# Genesis_giraffe.net
KiCad netlist of a schematic drawn in EAGLE
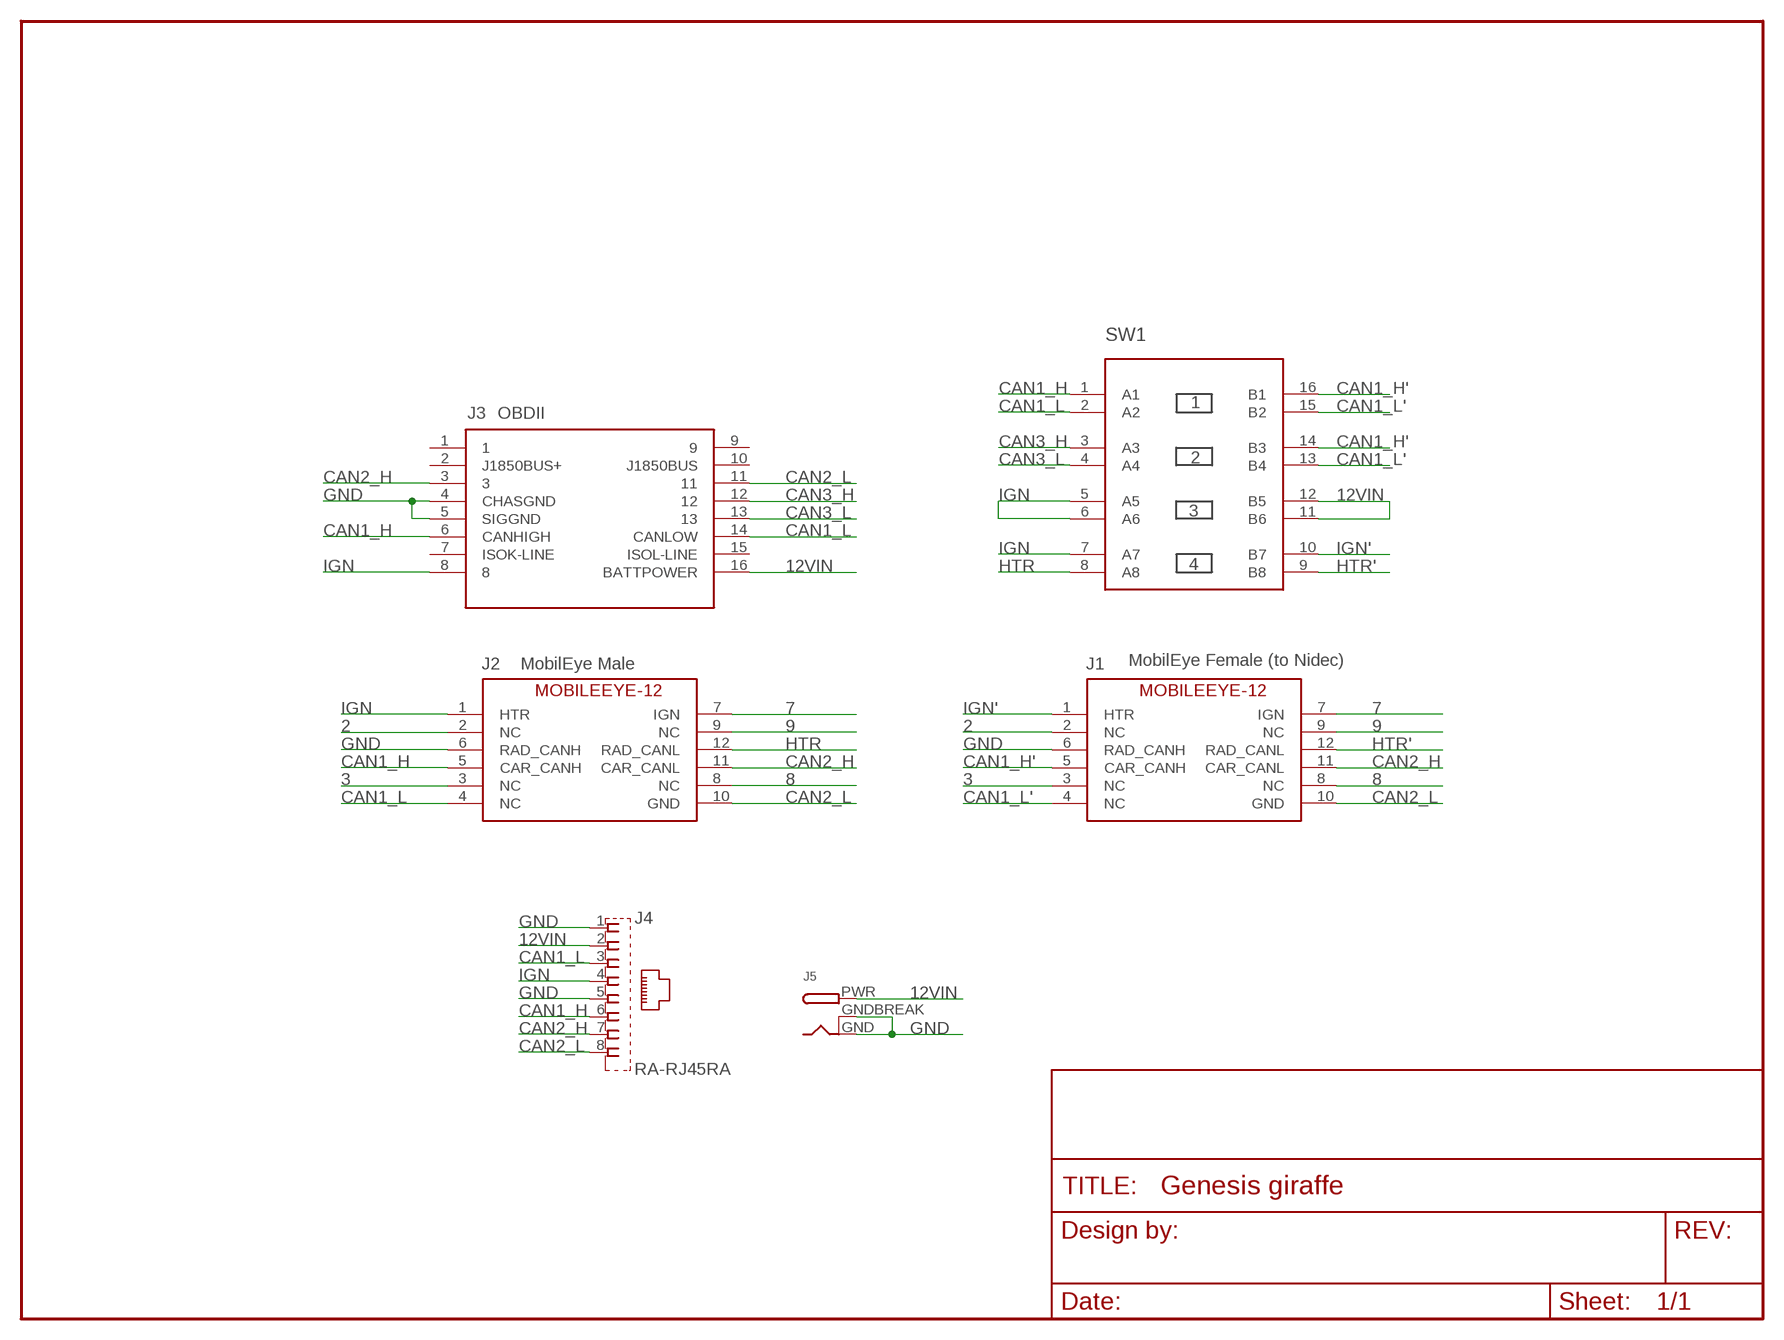
[diagram p0: schematic, sheet 1]

(export (version "E")
  (design (tool "Eeschema 10.0.6"))
  (components
    (comp (ref "FRAME1")
      (value "FRAME-LETTERNO_PACKAGE")
      (footprint "eagle-import:DUMMY")
      (fields (field (name "DESIGNER") "Nobody"))
      (libsource (lib "eagle-import") (part "FRAME-LETTERNO_PACKAGE"))
    )
    (comp (ref "J1")
      (value "MOBILEEYE-12FEMALE")
      (footprint "eagle-import:2X6-TE-FEMALE")
      (libsource (lib "eagle-import") (part "MOBILEEYE-12FEMALE"))
    )
    (comp (ref "J2")
      (value "MOBILEEYE-12MALE")
      (footprint "eagle-import:2X6-TE-RA")
      (libsource (lib "eagle-import") (part "MOBILEEYE-12MALE"))
    )
    (comp (ref "J3")
      (value "COMMA.AI_OBDII-FEMALE")
      (footprint "eagle-import:COMMA.AI_2X6-TE-FEMALE_NEW1")
      (libsource (lib "eagle-import") (part "COMMA.AI_OBDII-FEMALE"))
    )
    (comp (ref "J4")
      (value "RA-RJ45RA")
      (footprint "eagle-import:RA-RJ45")
      (libsource (lib "eagle-import") (part "RA-RJ45RA"))
    )
    (comp (ref "J5")
      (value "DCBARRELPTH")
      (footprint "eagle-import:DCJACK_2MM_PTH")
      (libsource (lib "eagle-import") (part "DCBARRELPTH"))
    )
    (comp (ref "SW1")
      (value "4XDPSTSMT")
      (footprint "eagle-import:4-DPST")
      (libsource (lib "eagle-import") (part "4XDPSTSMT"))
    )
  )
  (nets
    (net (code "1") (name "/2") (class "Default")
      (node (ref "J1") (pin "2") (pinfunction "NC_2") (pintype "bidirectional"))
      (node (ref "J2") (pin "2") (pinfunction "NC_2") (pintype "bidirectional"))
    )
    (net (code "2") (name "/3") (class "Default")
      (node (ref "J1") (pin "3") (pinfunction "NC_3") (pintype "bidirectional"))
      (node (ref "J2") (pin "3") (pinfunction "NC_3") (pintype "bidirectional"))
    )
    (net (code "3") (name "/7") (class "Default")
      (node (ref "J1") (pin "7") (pinfunction "IGN_7") (pintype "bidirectional"))
      (node (ref "J2") (pin "7") (pinfunction "IGN_7") (pintype "bidirectional"))
    )
    (net (code "4") (name "/8") (class "Default")
      (node (ref "J1") (pin "8") (pinfunction "NC_8") (pintype "bidirectional"))
      (node (ref "J2") (pin "8") (pinfunction "NC_8") (pintype "bidirectional"))
    )
    (net (code "5") (name "/9") (class "Default")
      (node (ref "J1") (pin "9") (pinfunction "NC_9") (pintype "bidirectional"))
      (node (ref "J2") (pin "9") (pinfunction "NC_9") (pintype "bidirectional"))
    )
    (net (code "6") (name "/12VIN") (class "Default")
      (node (ref "J3") (pin "16") (pinfunction "BATTPOWER_16") (pintype "bidirectional"))
      (node (ref "J4") (pin "2") (pinfunction "2_2") (pintype "passive"))
      (node (ref "J5") (pin "PWR") (pinfunction "PWR_PWR") (pintype "power_in"))
      (node (ref "SW1") (pin "11") (pinfunction "B6_11") (pintype "bidirectional"))
      (node (ref "SW1") (pin "12") (pinfunction "B5_12") (pintype "bidirectional"))
    )
    (net (code "7") (name "/CAN1_H") (class "Default")
      (node (ref "J2") (pin "5") (pinfunction "CAR_CANH_5") (pintype "bidirectional"))
      (node (ref "J3") (pin "6") (pinfunction "CANHIGH_6") (pintype "bidirectional"))
      (node (ref "J4") (pin "6") (pinfunction "6_6") (pintype "passive"))
      (node (ref "SW1") (pin "1") (pinfunction "A1_1") (pintype "bidirectional"))
    )
    (net (code "8") (name "/CAN1_H'") (class "Default")
      (node (ref "J1") (pin "5") (pinfunction "CAR_CANH_5") (pintype "bidirectional"))
      (node (ref "SW1") (pin "14") (pinfunction "B3_14") (pintype "bidirectional"))
      (node (ref "SW1") (pin "16") (pinfunction "B1_16") (pintype "bidirectional"))
    )
    (net (code "9") (name "/CAN1_L") (class "Default")
      (node (ref "J2") (pin "4") (pinfunction "NC_4") (pintype "bidirectional"))
      (node (ref "J3") (pin "14") (pinfunction "CANLOW_14") (pintype "bidirectional"))
      (node (ref "J4") (pin "3") (pinfunction "3_3") (pintype "passive"))
      (node (ref "SW1") (pin "2") (pinfunction "A2_2") (pintype "bidirectional"))
    )
    (net (code "10") (name "/CAN1_L'") (class "Default")
      (node (ref "J1") (pin "4") (pinfunction "NC_4") (pintype "bidirectional"))
      (node (ref "SW1") (pin "13") (pinfunction "B4_13") (pintype "bidirectional"))
      (node (ref "SW1") (pin "15") (pinfunction "B2_15") (pintype "bidirectional"))
    )
    (net (code "11") (name "/CAN2_H") (class "Default")
      (node (ref "J1") (pin "11") (pinfunction "CAR_CANL_11") (pintype "bidirectional"))
      (node (ref "J2") (pin "11") (pinfunction "CAR_CANL_11") (pintype "bidirectional"))
      (node (ref "J3") (pin "3") (pinfunction "3_3") (pintype "bidirectional"))
      (node (ref "J4") (pin "7") (pinfunction "7_7") (pintype "passive"))
    )
    (net (code "12") (name "/CAN2_L") (class "Default")
      (node (ref "J1") (pin "10") (pinfunction "GND_10") (pintype "bidirectional"))
      (node (ref "J2") (pin "10") (pinfunction "GND_10") (pintype "bidirectional"))
      (node (ref "J3") (pin "11") (pinfunction "11_11") (pintype "bidirectional"))
      (node (ref "J4") (pin "8") (pinfunction "8_8") (pintype "passive"))
    )
    (net (code "13") (name "/CAN3_H") (class "Default")
      (node (ref "J3") (pin "12") (pinfunction "12_12") (pintype "bidirectional"))
      (node (ref "SW1") (pin "3") (pinfunction "A3_3") (pintype "bidirectional"))
    )
    (net (code "14") (name "/CAN3_L") (class "Default")
      (node (ref "J3") (pin "13") (pinfunction "13_13") (pintype "bidirectional"))
      (node (ref "SW1") (pin "4") (pinfunction "A4_4") (pintype "bidirectional"))
    )
    (net (code "15") (name "/GND") (class "Default")
      (node (ref "J1") (pin "6") (pinfunction "RAD_CANH_6") (pintype "bidirectional"))
      (node (ref "J2") (pin "6") (pinfunction "RAD_CANH_6") (pintype "bidirectional"))
      (node (ref "J3") (pin "4") (pinfunction "CHASGND_4") (pintype "bidirectional"))
      (node (ref "J3") (pin "5") (pinfunction "SIGGND_5") (pintype "bidirectional"))
      (node (ref "J4") (pin "1") (pinfunction "1_1") (pintype "passive"))
      (node (ref "J4") (pin "5") (pinfunction "5_5") (pintype "passive"))
      (node (ref "J5") (pin "GND") (pinfunction "GND_GND") (pintype "power_in"))
      (node (ref "J5") (pin "GNDBREAK") (pinfunction "GNDBREAK_GNDBREAK") (pintype "power_in"))
    )
    (net (code "16") (name "/HTR") (class "Default")
      (node (ref "J2") (pin "12") (pinfunction "RAD_CANL_12") (pintype "bidirectional"))
      (node (ref "SW1") (pin "8") (pinfunction "A8_8") (pintype "bidirectional"))
    )
    (net (code "17") (name "/HTR'") (class "Default")
      (node (ref "J1") (pin "12") (pinfunction "RAD_CANL_12") (pintype "bidirectional"))
      (node (ref "SW1") (pin "9") (pinfunction "B8_9") (pintype "bidirectional"))
    )
    (net (code "18") (name "/IGN") (class "Default")
      (node (ref "J2") (pin "1") (pinfunction "HTR_1") (pintype "bidirectional"))
      (node (ref "J3") (pin "8") (pinfunction "8_8") (pintype "bidirectional"))
      (node (ref "J4") (pin "4") (pinfunction "4_4") (pintype "passive"))
      (node (ref "SW1") (pin "5") (pinfunction "A5_5") (pintype "bidirectional"))
      (node (ref "SW1") (pin "6") (pinfunction "A6_6") (pintype "bidirectional"))
      (node (ref "SW1") (pin "7") (pinfunction "A7_7") (pintype "bidirectional"))
    )
    (net (code "19") (name "/IGN'") (class "Default")
      (node (ref "J1") (pin "1") (pinfunction "HTR_1") (pintype "bidirectional"))
      (node (ref "SW1") (pin "10") (pinfunction "B7_10") (pintype "bidirectional"))
    )
    (net (code "20") (name "unconnected-(J3-ISOK-LINE-Pad7)") (class "Default")
      (node (ref "J3") (pin "7") (pinfunction "ISOK-LINE_7") (pintype "bidirectional"))
    )
    (net (code "21") (name "unconnected-(J3-ISOL-LINE-Pad15)") (class "Default")
      (node (ref "J3") (pin "15") (pinfunction "ISOL-LINE_15") (pintype "bidirectional"))
    )
    (net (code "22") (name "unconnected-(J3-J1850BUS+-Pad2)") (class "Default")
      (node (ref "J3") (pin "2") (pinfunction "J1850BUS+_2") (pintype "bidirectional"))
    )
    (net (code "23") (name "unconnected-(J3-J1850BUS-Pad10)") (class "Default")
      (node (ref "J3") (pin "10") (pinfunction "J1850BUS_10") (pintype "bidirectional"))
    )
    (net (code "24") (name "unconnected-(J3-Pad1)") (class "Default")
      (node (ref "J3") (pin "1") (pinfunction "1_1") (pintype "bidirectional"))
    )
    (net (code "25") (name "unconnected-(J3-Pad9)") (class "Default")
      (node (ref "J3") (pin "9") (pinfunction "9_9") (pintype "bidirectional"))
    )
  )
)
